# db44breakout.net
KiCad netlist of a schematic drawn in Altium Designer
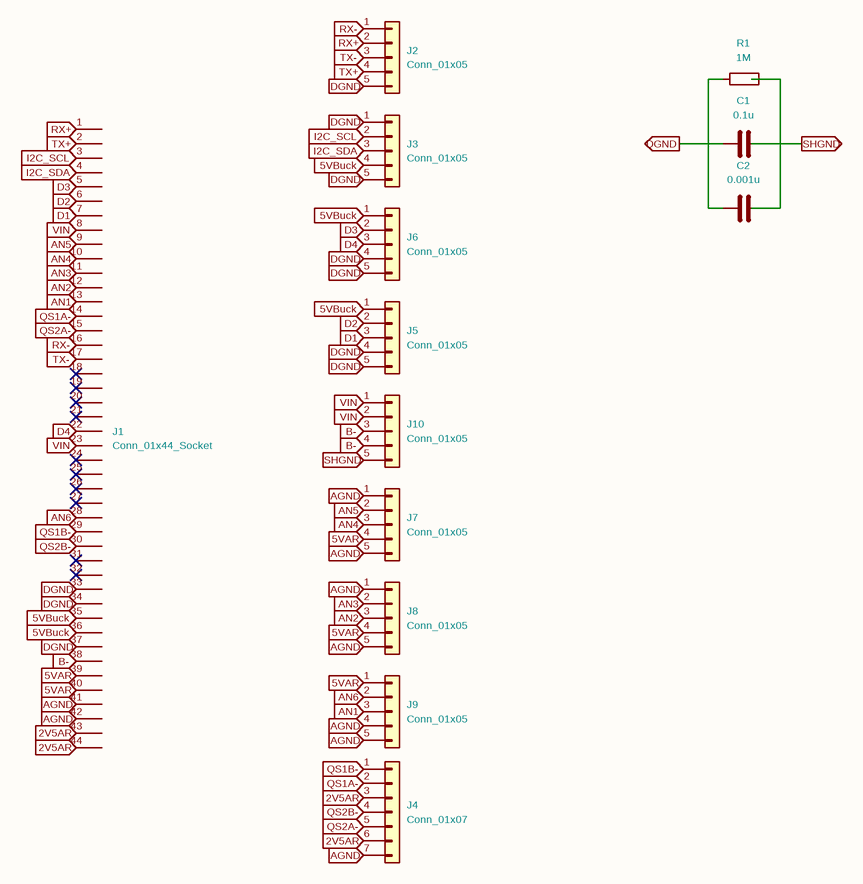
[diagram p0: db44breakout.SchDoc]

(export (version "E")
  (design (tool "Eeschema 10.0.6"))
  (components
    (comp (ref "C1")
      (value "0.1u")
      (description "Unpolarized capacitor")
      (libsource (lib "Device") (part "C"))
    )
    (comp (ref "C2")
      (value "0.001u")
      (description "Unpolarized capacitor")
      (libsource (lib "Device") (part "C"))
    )
    (comp (ref "J1")
      (value "Conn_01x44_Socket")
      (description "\"Generic connector, single row, 01x44, script generated\"")
      (libsource (lib "Connector") (part "Conn_01x44_Socket"))
    )
    (comp (ref "J2") (value "Conn_01x05") (libsource (lib "Connector_Generic") (part "Conn_01x05")))
    (comp (ref "J3") (value "Conn_01x05") (libsource (lib "Connector_Generic") (part "Conn_01x05")))
    (comp (ref "J4") (value "Conn_01x07") (libsource (lib "Connector_Generic") (part "Conn_01x07")))
    (comp (ref "J5") (value "Conn_01x05") (libsource (lib "Connector_Generic") (part "Conn_01x05")))
    (comp (ref "J6") (value "Conn_01x05") (libsource (lib "Connector_Generic") (part "Conn_01x05")))
    (comp (ref "J7") (value "Conn_01x05") (libsource (lib "Connector_Generic") (part "Conn_01x05")))
    (comp (ref "J8") (value "Conn_01x05") (libsource (lib "Connector_Generic") (part "Conn_01x05")))
    (comp (ref "J9") (value "Conn_01x05") (libsource (lib "Connector_Generic") (part "Conn_01x05")))
    (comp (ref "J10") (value "Conn_01x05") (libsource (lib "Connector_Generic") (part "Conn_01x05")))
    (comp (ref "R1") (value "1M") (description "Resistor") (libsource (lib "Device") (part "R")))
  )
  (nets
    (net (code "1") (name "/2V5AR") (class "Default")
      (node (ref "J1") (pin "43") (pinfunction "Pin_43_43") (pintype "passive"))
      (node (ref "J1") (pin "44") (pinfunction "Pin_44_44") (pintype "passive"))
      (node (ref "J4") (pin "3") (pinfunction "Pin_3_3") (pintype "passive"))
      (node (ref "J4") (pin "6") (pinfunction "Pin_6_6") (pintype "passive"))
    )
    (net (code "2") (name "/5VAR") (class "Default")
      (node (ref "J1") (pin "39") (pinfunction "Pin_39_39") (pintype "passive"))
      (node (ref "J1") (pin "40") (pinfunction "Pin_40_40") (pintype "passive"))
      (node (ref "J7") (pin "4") (pinfunction "Pin_4_4") (pintype "passive"))
      (node (ref "J8") (pin "4") (pinfunction "Pin_4_4") (pintype "passive"))
      (node (ref "J9") (pin "1") (pinfunction "Pin_1_1") (pintype "passive"))
    )
    (net (code "3") (name "/5VBuck") (class "Default")
      (node (ref "J1") (pin "35") (pinfunction "Pin_35_35") (pintype "passive"))
      (node (ref "J1") (pin "36") (pinfunction "Pin_36_36") (pintype "passive"))
      (node (ref "J3") (pin "4") (pinfunction "Pin_4_4") (pintype "passive"))
      (node (ref "J5") (pin "1") (pinfunction "Pin_1_1") (pintype "passive"))
      (node (ref "J6") (pin "1") (pinfunction "Pin_1_1") (pintype "passive"))
    )
    (net (code "4") (name "/AGND") (class "Default")
      (node (ref "J1") (pin "41") (pinfunction "Pin_41_41") (pintype "passive"))
      (node (ref "J1") (pin "42") (pinfunction "Pin_42_42") (pintype "passive"))
      (node (ref "J4") (pin "7") (pinfunction "Pin_7_7") (pintype "passive"))
      (node (ref "J7") (pin "1") (pinfunction "Pin_1_1") (pintype "passive"))
      (node (ref "J7") (pin "5") (pinfunction "Pin_5_5") (pintype "passive"))
      (node (ref "J8") (pin "1") (pinfunction "Pin_1_1") (pintype "passive"))
      (node (ref "J8") (pin "5") (pinfunction "Pin_5_5") (pintype "passive"))
      (node (ref "J9") (pin "4") (pinfunction "Pin_4_4") (pintype "passive"))
      (node (ref "J9") (pin "5") (pinfunction "Pin_5_5") (pintype "passive"))
    )
    (net (code "5") (name "/AN1") (class "Default")
      (node (ref "J1") (pin "13") (pinfunction "Pin_13_13") (pintype "passive"))
      (node (ref "J9") (pin "3") (pinfunction "Pin_3_3") (pintype "passive"))
    )
    (net (code "6") (name "/AN2") (class "Default")
      (node (ref "J1") (pin "12") (pinfunction "Pin_12_12") (pintype "passive"))
      (node (ref "J8") (pin "3") (pinfunction "Pin_3_3") (pintype "passive"))
    )
    (net (code "7") (name "/AN3") (class "Default")
      (node (ref "J1") (pin "11") (pinfunction "Pin_11_11") (pintype "passive"))
      (node (ref "J8") (pin "2") (pinfunction "Pin_2_2") (pintype "passive"))
    )
    (net (code "8") (name "/AN4") (class "Default")
      (node (ref "J1") (pin "10") (pinfunction "Pin_10_10") (pintype "passive"))
      (node (ref "J7") (pin "3") (pinfunction "Pin_3_3") (pintype "passive"))
    )
    (net (code "9") (name "/AN5") (class "Default")
      (node (ref "J1") (pin "9") (pinfunction "Pin_9_9") (pintype "passive"))
      (node (ref "J7") (pin "2") (pinfunction "Pin_2_2") (pintype "passive"))
    )
    (net (code "10") (name "/AN6") (class "Default")
      (node (ref "J1") (pin "28") (pinfunction "Pin_28_28") (pintype "passive"))
      (node (ref "J9") (pin "2") (pinfunction "Pin_2_2") (pintype "passive"))
    )
    (net (code "11") (name "/B-") (class "Default")
      (node (ref "J1") (pin "38") (pinfunction "Pin_38_38") (pintype "passive"))
      (node (ref "J10") (pin "3") (pinfunction "Pin_3_3") (pintype "passive"))
      (node (ref "J10") (pin "4") (pinfunction "Pin_4_4") (pintype "passive"))
    )
    (net (code "12") (name "/D1") (class "Default")
      (node (ref "J1") (pin "7") (pinfunction "Pin_7_7") (pintype "passive"))
      (node (ref "J5") (pin "3") (pinfunction "Pin_3_3") (pintype "passive"))
    )
    (net (code "13") (name "/D2") (class "Default")
      (node (ref "J1") (pin "6") (pinfunction "Pin_6_6") (pintype "passive"))
      (node (ref "J5") (pin "2") (pinfunction "Pin_2_2") (pintype "passive"))
    )
    (net (code "14") (name "/D3") (class "Default")
      (node (ref "J1") (pin "5") (pinfunction "Pin_5_5") (pintype "passive"))
      (node (ref "J6") (pin "2") (pinfunction "Pin_2_2") (pintype "passive"))
    )
    (net (code "15") (name "/D4") (class "Default")
      (node (ref "J1") (pin "22") (pinfunction "Pin_22_22") (pintype "passive"))
      (node (ref "J6") (pin "3") (pinfunction "Pin_3_3") (pintype "passive"))
    )
    (net (code "16") (name "/DGND") (class "Default")
      (node (ref "C1") (pin "1") (pinfunction "1_1") (pintype "passive"))
      (node (ref "C2") (pin "2") (pinfunction "2_2") (pintype "passive"))
      (node (ref "J1") (pin "33") (pinfunction "Pin_33_33") (pintype "passive"))
      (node (ref "J1") (pin "34") (pinfunction "Pin_34_34") (pintype "passive"))
      (node (ref "J1") (pin "37") (pinfunction "Pin_37_37") (pintype "passive"))
      (node (ref "J2") (pin "5") (pinfunction "Pin_5_5") (pintype "passive"))
      (node (ref "J3") (pin "1") (pinfunction "Pin_1_1") (pintype "passive"))
      (node (ref "J3") (pin "5") (pinfunction "Pin_5_5") (pintype "passive"))
      (node (ref "J5") (pin "4") (pinfunction "Pin_4_4") (pintype "passive"))
      (node (ref "J5") (pin "5") (pinfunction "Pin_5_5") (pintype "passive"))
      (node (ref "J6") (pin "4") (pinfunction "Pin_4_4") (pintype "passive"))
      (node (ref "J6") (pin "5") (pinfunction "Pin_5_5") (pintype "passive"))
      (node (ref "R1") (pin "1") (pinfunction "1_1") (pintype "passive"))
    )
    (net (code "17") (name "/I2C_SCL") (class "Default")
      (node (ref "J1") (pin "3") (pinfunction "Pin_3_3") (pintype "passive"))
      (node (ref "J3") (pin "2") (pinfunction "Pin_2_2") (pintype "passive"))
    )
    (net (code "18") (name "/I2C_SDA") (class "Default")
      (node (ref "J1") (pin "4") (pinfunction "Pin_4_4") (pintype "passive"))
      (node (ref "J3") (pin "3") (pinfunction "Pin_3_3") (pintype "passive"))
    )
    (net (code "19") (name "/QS1A-") (class "Default")
      (node (ref "J1") (pin "14") (pinfunction "Pin_14_14") (pintype "passive"))
      (node (ref "J4") (pin "2") (pinfunction "Pin_2_2") (pintype "passive"))
    )
    (net (code "20") (name "/QS1B-") (class "Default")
      (node (ref "J1") (pin "29") (pinfunction "Pin_29_29") (pintype "passive"))
      (node (ref "J4") (pin "1") (pinfunction "Pin_1_1") (pintype "passive"))
    )
    (net (code "21") (name "/QS2A-") (class "Default")
      (node (ref "J1") (pin "15") (pinfunction "Pin_15_15") (pintype "passive"))
      (node (ref "J4") (pin "5") (pinfunction "Pin_5_5") (pintype "passive"))
    )
    (net (code "22") (name "/QS2B-") (class "Default")
      (node (ref "J1") (pin "30") (pinfunction "Pin_30_30") (pintype "passive"))
      (node (ref "J4") (pin "4") (pinfunction "Pin_4_4") (pintype "passive"))
    )
    (net (code "23") (name "/RX+") (class "Default")
      (node (ref "J1") (pin "1") (pinfunction "Pin_1_1") (pintype "passive"))
      (node (ref "J2") (pin "2") (pinfunction "Pin_2_2") (pintype "passive"))
    )
    (net (code "24") (name "/RX-") (class "Default")
      (node (ref "J1") (pin "16") (pinfunction "Pin_16_16") (pintype "passive"))
      (node (ref "J2") (pin "1") (pinfunction "Pin_1_1") (pintype "passive"))
    )
    (net (code "25") (name "/SHGND") (class "Default")
      (node (ref "C1") (pin "2") (pinfunction "2_2") (pintype "passive"))
      (node (ref "C2") (pin "1") (pinfunction "1_1") (pintype "passive"))
      (node (ref "J10") (pin "5") (pinfunction "Pin_5_5") (pintype "passive"))
      (node (ref "R1") (pin "2") (pinfunction "2_2") (pintype "passive"))
    )
    (net (code "26") (name "/TX+") (class "Default")
      (node (ref "J1") (pin "2") (pinfunction "Pin_2_2") (pintype "passive"))
      (node (ref "J2") (pin "4") (pinfunction "Pin_4_4") (pintype "passive"))
    )
    (net (code "27") (name "/TX-") (class "Default")
      (node (ref "J1") (pin "17") (pinfunction "Pin_17_17") (pintype "passive"))
      (node (ref "J2") (pin "3") (pinfunction "Pin_3_3") (pintype "passive"))
    )
    (net (code "28") (name "/VIN") (class "Default")
      (node (ref "J1") (pin "23") (pinfunction "Pin_23_23") (pintype "passive"))
      (node (ref "J1") (pin "8") (pinfunction "Pin_8_8") (pintype "passive"))
      (node (ref "J10") (pin "1") (pinfunction "Pin_1_1") (pintype "passive"))
      (node (ref "J10") (pin "2") (pinfunction "Pin_2_2") (pintype "passive"))
    )
    (net (code "29") (name "unconnected-(J1-Pin_18-Pad18)") (class "Default")
      (node (ref "J1") (pin "18") (pinfunction "Pin_18_18") (pintype "passive+no_connect"))
    )
    (net (code "30") (name "unconnected-(J1-Pin_19-Pad19)") (class "Default")
      (node (ref "J1") (pin "19") (pinfunction "Pin_19_19") (pintype "passive+no_connect"))
    )
    (net (code "31") (name "unconnected-(J1-Pin_20-Pad20)") (class "Default")
      (node (ref "J1") (pin "20") (pinfunction "Pin_20_20") (pintype "passive+no_connect"))
    )
    (net (code "32") (name "unconnected-(J1-Pin_21-Pad21)") (class "Default")
      (node (ref "J1") (pin "21") (pinfunction "Pin_21_21") (pintype "passive+no_connect"))
    )
    (net (code "33") (name "unconnected-(J1-Pin_24-Pad24)") (class "Default")
      (node (ref "J1") (pin "24") (pinfunction "Pin_24_24") (pintype "passive+no_connect"))
    )
    (net (code "34") (name "unconnected-(J1-Pin_25-Pad25)") (class "Default")
      (node (ref "J1") (pin "25") (pinfunction "Pin_25_25") (pintype "passive+no_connect"))
    )
    (net (code "35") (name "unconnected-(J1-Pin_26-Pad26)") (class "Default")
      (node (ref "J1") (pin "26") (pinfunction "Pin_26_26") (pintype "passive+no_connect"))
    )
    (net (code "36") (name "unconnected-(J1-Pin_27-Pad27)") (class "Default")
      (node (ref "J1") (pin "27") (pinfunction "Pin_27_27") (pintype "passive+no_connect"))
    )
    (net (code "37") (name "unconnected-(J1-Pin_31-Pad31)") (class "Default")
      (node (ref "J1") (pin "31") (pinfunction "Pin_31_31") (pintype "passive+no_connect"))
    )
    (net (code "38") (name "unconnected-(J1-Pin_32-Pad32)") (class "Default")
      (node (ref "J1") (pin "32") (pinfunction "Pin_32_32") (pintype "passive+no_connect"))
    )
  )
)
